# musicbox.net
KiCad netlist of a schematic drawn in EAGLE
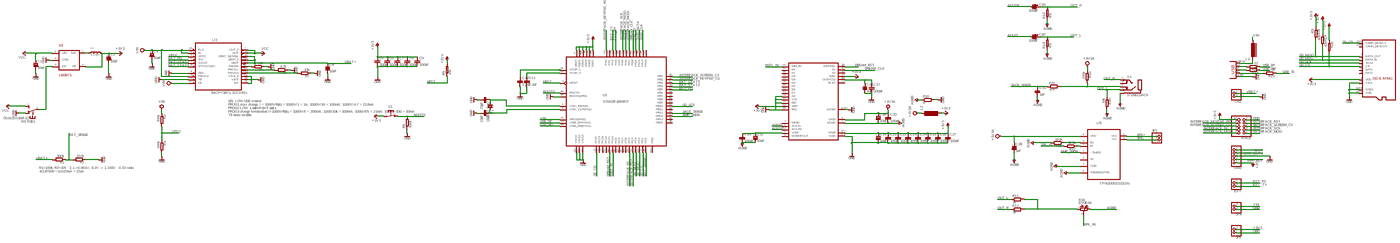
[diagram p0: schematic, sheet 1, overview]
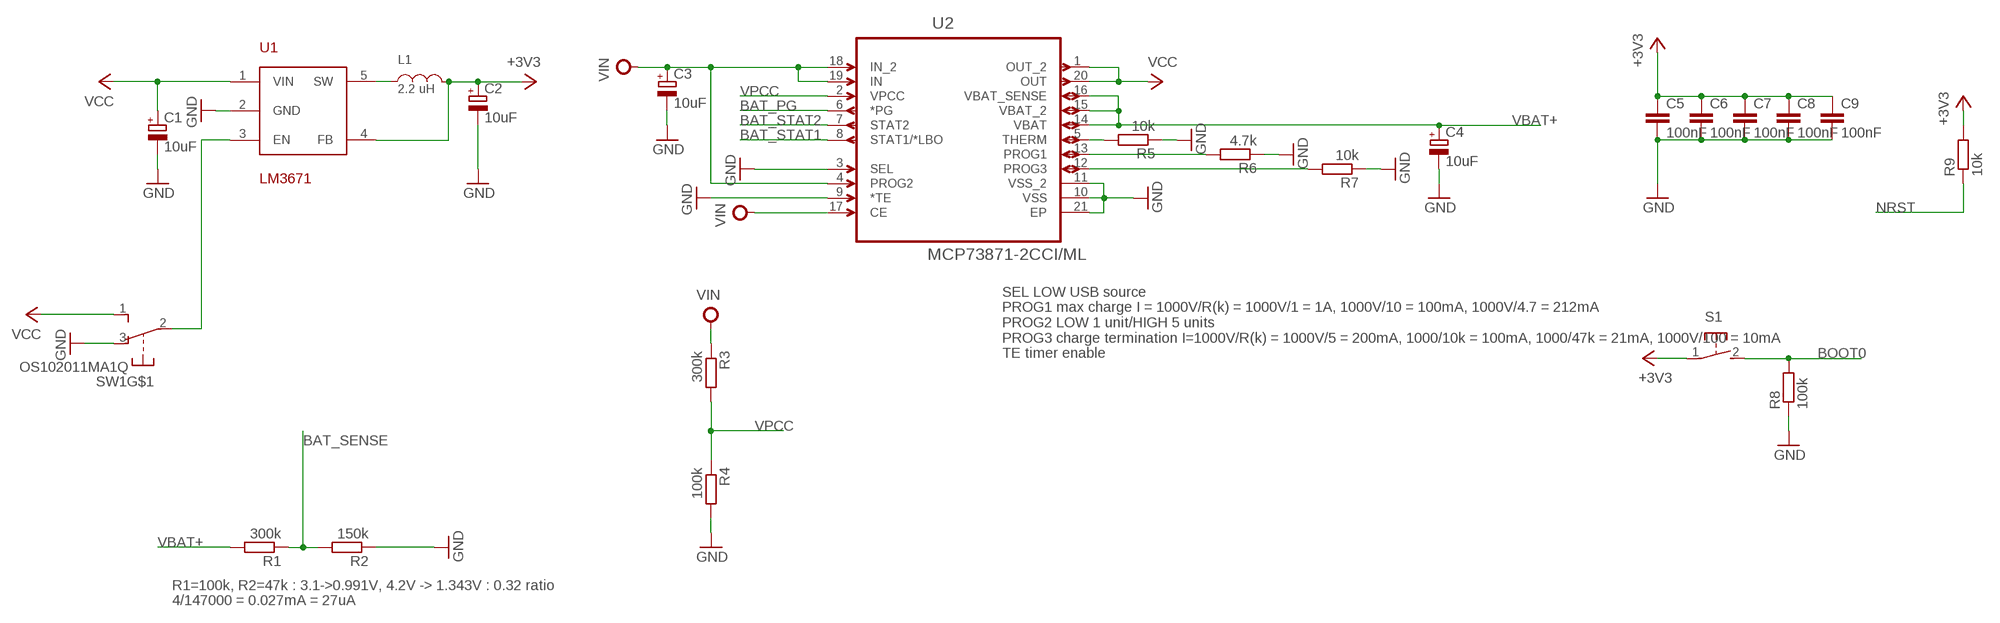
[diagram p1: schematic, sheet 1, part 1 of 4]
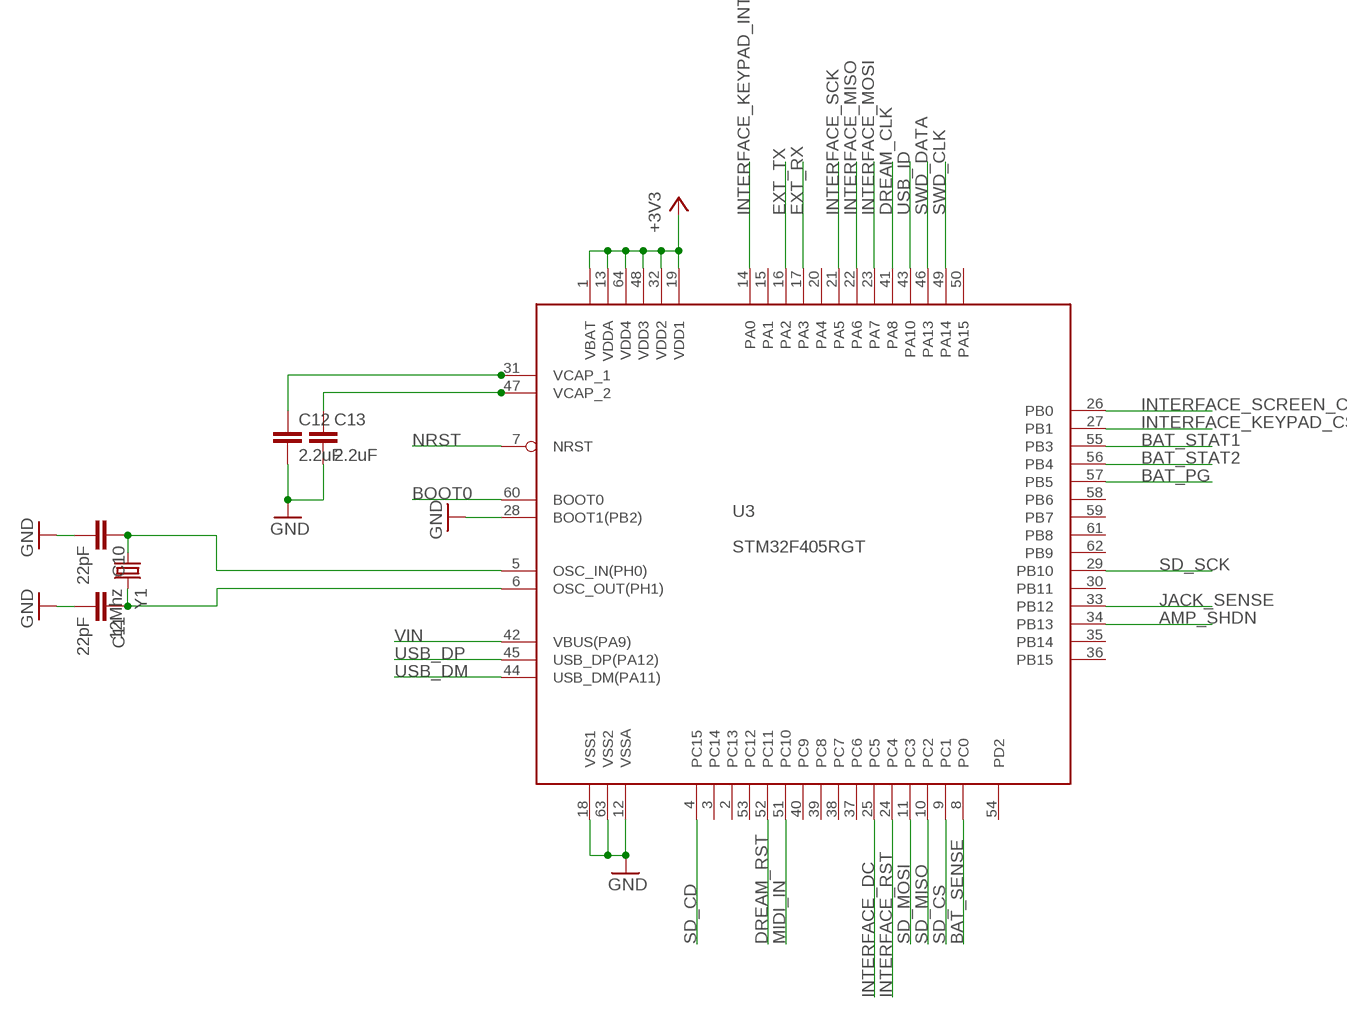
[diagram p2: schematic, sheet 1, part 2 of 4]
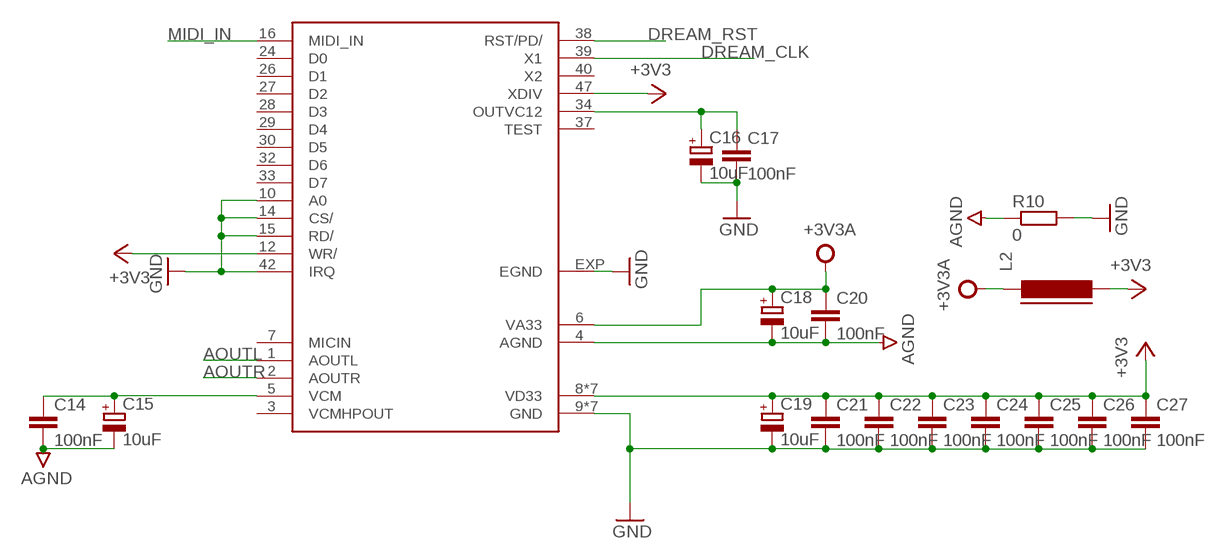
[diagram p3: schematic, sheet 1, part 3 of 4]
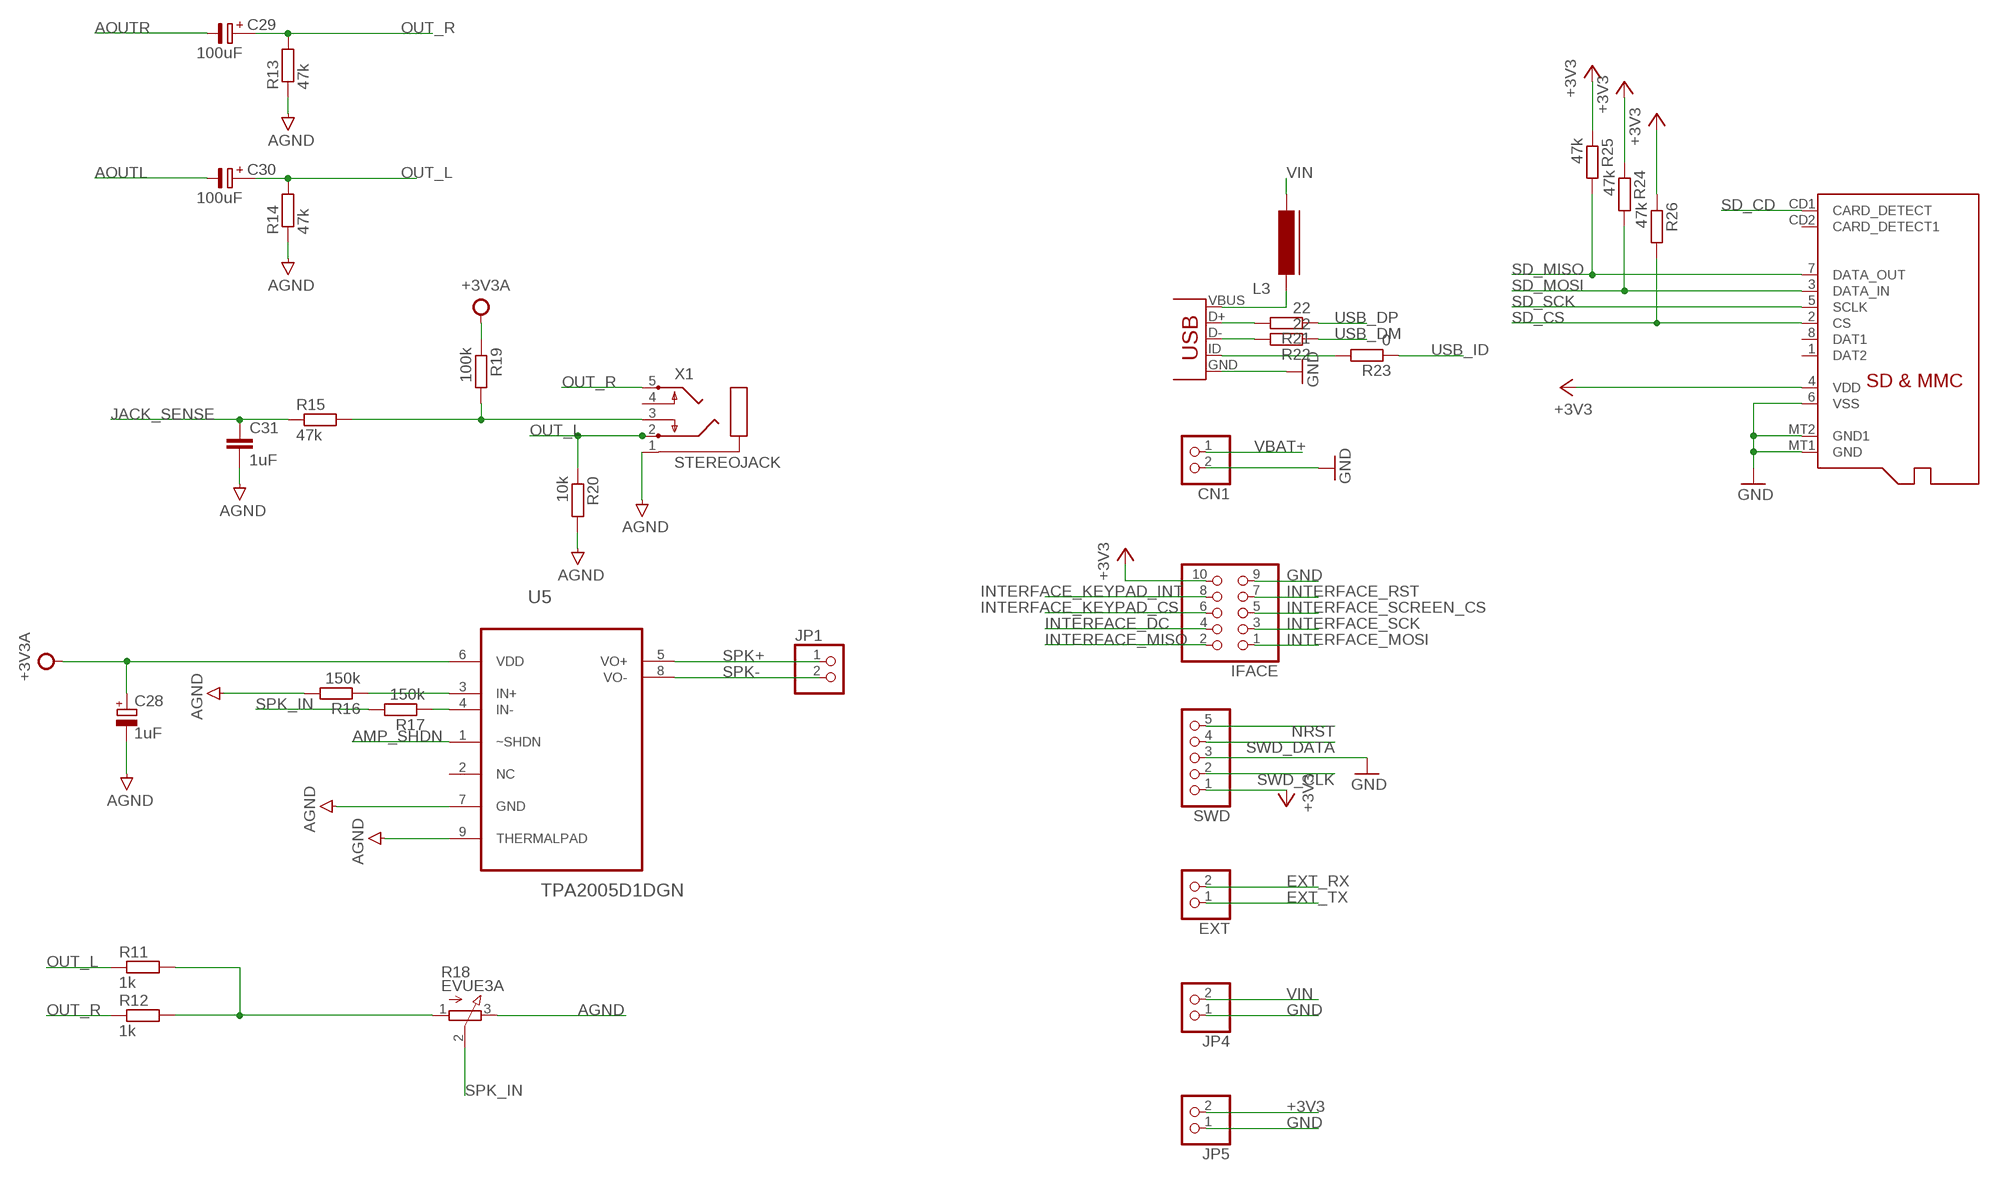
[diagram p4: schematic, sheet 1, part 4 of 4]

(export (version "E")
  (design (tool "Eeschema 10.0.6"))
  (components
    (comp (ref "C1")
      (value "10uF")
      (footprint "eagle-import:A_3216-18R")
      (libsource (lib "eagle-import") (part "CPOL-EUA/3216-18R"))
    )
    (comp (ref "C2")
      (value "10uF")
      (footprint "eagle-import:A_3216-18R")
      (libsource (lib "eagle-import") (part "CPOL-EUA/3216-18R"))
    )
    (comp (ref "C3")
      (value "10uF")
      (footprint "eagle-import:A_3216-18R")
      (libsource (lib "eagle-import") (part "CPOL-EUA/3216-18R"))
    )
    (comp (ref "C4")
      (value "10uF")
      (footprint "eagle-import:A_3216-18R")
      (libsource (lib "eagle-import") (part "CPOL-EUA/3216-18R"))
    )
    (comp (ref "C5")
      (value "100nF")
      (footprint "eagle-import:C0603K")
      (libsource (lib "eagle-import") (part "C-EUC0603K"))
    )
    (comp (ref "C6")
      (value "100nF")
      (footprint "eagle-import:C0603K")
      (libsource (lib "eagle-import") (part "C-EUC0603K"))
    )
    (comp (ref "C7")
      (value "100nF")
      (footprint "eagle-import:C0603K")
      (libsource (lib "eagle-import") (part "C-EUC0603K"))
    )
    (comp (ref "C8")
      (value "100nF")
      (footprint "eagle-import:C0603K")
      (libsource (lib "eagle-import") (part "C-EUC0603K"))
    )
    (comp (ref "C9")
      (value "100nF")
      (footprint "eagle-import:C0603K")
      (libsource (lib "eagle-import") (part "C-EUC0603K"))
    )
    (comp (ref "C10")
      (value "22pF")
      (footprint "eagle-import:C0603K")
      (libsource (lib "eagle-import") (part "C-EUC0603K"))
    )
    (comp (ref "C11")
      (value "22pF")
      (footprint "eagle-import:C0603K")
      (libsource (lib "eagle-import") (part "C-EUC0603K"))
    )
    (comp (ref "C12")
      (value "2.2uF")
      (footprint "eagle-import:C0603K")
      (libsource (lib "eagle-import") (part "C-EUC0603K"))
    )
    (comp (ref "C13")
      (value "2.2uF")
      (footprint "eagle-import:C0603K")
      (libsource (lib "eagle-import") (part "C-EUC0603K"))
    )
    (comp (ref "C14")
      (value "100nF")
      (footprint "eagle-import:C0603K")
      (libsource (lib "eagle-import") (part "C-EUC0603K"))
    )
    (comp (ref "C15")
      (value "10uF")
      (footprint "eagle-import:A_3216-18R")
      (libsource (lib "eagle-import") (part "CPOL-EUA/3216-18R"))
    )
    (comp (ref "C16")
      (value "10uF")
      (footprint "eagle-import:A_3216-18R")
      (libsource (lib "eagle-import") (part "CPOL-EUA/3216-18R"))
    )
    (comp (ref "C17")
      (value "100nF")
      (footprint "eagle-import:C0603K")
      (libsource (lib "eagle-import") (part "C-EUC0603K"))
    )
    (comp (ref "C18")
      (value "10uF")
      (footprint "eagle-import:A_3216-18R")
      (libsource (lib "eagle-import") (part "CPOL-EUA/3216-18R"))
    )
    (comp (ref "C19")
      (value "10uF")
      (footprint "eagle-import:A_3216-18R")
      (libsource (lib "eagle-import") (part "CPOL-EUA/3216-18R"))
    )
    (comp (ref "C20")
      (value "100nF")
      (footprint "eagle-import:C0603K")
      (libsource (lib "eagle-import") (part "C-EUC0603K"))
    )
    (comp (ref "C21")
      (value "100nF")
      (footprint "eagle-import:C0603K")
      (libsource (lib "eagle-import") (part "C-EUC0603K"))
    )
    (comp (ref "C22")
      (value "100nF")
      (footprint "eagle-import:C0603K")
      (libsource (lib "eagle-import") (part "C-EUC0603K"))
    )
    (comp (ref "C23")
      (value "100nF")
      (footprint "eagle-import:C0603K")
      (libsource (lib "eagle-import") (part "C-EUC0603K"))
    )
    (comp (ref "C24")
      (value "100nF")
      (footprint "eagle-import:C0603K")
      (libsource (lib "eagle-import") (part "C-EUC0603K"))
    )
    (comp (ref "C25")
      (value "100nF")
      (footprint "eagle-import:C0603K")
      (libsource (lib "eagle-import") (part "C-EUC0603K"))
    )
    (comp (ref "C26")
      (value "100nF")
      (footprint "eagle-import:C0603K")
      (libsource (lib "eagle-import") (part "C-EUC0603K"))
    )
    (comp (ref "C27")
      (value "100nF")
      (footprint "eagle-import:C0603K")
      (libsource (lib "eagle-import") (part "C-EUC0603K"))
    )
    (comp (ref "C28")
      (value "1uF")
      (footprint "eagle-import:A_3216-18R")
      (libsource (lib "eagle-import") (part "CPOL-EUA/3216-18R"))
    )
    (comp (ref "C29")
      (value "100uF")
      (footprint "eagle-import:SV-B")
      (libsource (lib "eagle-import") (part "C-PR-SMD-SV-B"))
    )
    (comp (ref "C30")
      (value "100uF")
      (footprint "eagle-import:SV-B")
      (libsource (lib "eagle-import") (part "C-PR-SMD-SV-B"))
    )
    (comp (ref "C31")
      (value "1uF")
      (footprint "eagle-import:C0603K")
      (libsource (lib "eagle-import") (part "C-EUC0603K"))
    )
    (comp (ref "CN1")
      (value "JST_2PIN-THM")
      (footprint "eagle-import:JST-PH-2-THM")
      (libsource (lib "eagle-import") (part "JST_2PIN-THM"))
    )
    (comp (ref "EXT")
      (value "HEADER-1X2ROUND")
      (footprint "eagle-import:1X02_ROUND")
      (libsource (lib "eagle-import") (part "HEADER-1X2ROUND"))
    )
    (comp (ref "IFACE")
      (value "HEADER-2X5")
      (footprint "eagle-import:2X05")
      (libsource (lib "eagle-import") (part "HEADER-2X5"))
    )
    (comp (ref "JP1")
      (value "HEADER-1X2ROUND")
      (footprint "eagle-import:1X02_ROUND")
      (libsource (lib "eagle-import") (part "HEADER-1X2ROUND"))
    )
    (comp (ref "JP4")
      (value "HEADER-1X2ROUND")
      (footprint "eagle-import:1X02_ROUND")
      (libsource (lib "eagle-import") (part "HEADER-1X2ROUND"))
    )
    (comp (ref "JP5")
      (value "HEADER-1X2ROUND")
      (footprint "eagle-import:1X02_ROUND")
      (libsource (lib "eagle-import") (part "HEADER-1X2ROUND"))
    )
    (comp (ref "L1")
      (value "2.2 uH")
      (footprint "eagle-import:4X4MM")
      (libsource (lib "eagle-import") (part "L4X4MM"))
    )
    (comp (ref "L2")
      (value "FERRITE-0603")
      (footprint "eagle-import:FB603")
      (libsource (lib "eagle-import") (part "FERRITE-0603"))
    )
    (comp (ref "L3")
      (value "FERRITE-0603")
      (footprint "eagle-import:FB603")
      (libsource (lib "eagle-import") (part "FERRITE-0603"))
    )
    (comp (ref "R1")
      (value "300k")
      (footprint "eagle-import:R0603")
      (libsource (lib "eagle-import") (part "R-EU_R0603"))
    )
    (comp (ref "R2")
      (value "150k")
      (footprint "eagle-import:R0603")
      (libsource (lib "eagle-import") (part "R-EU_R0603"))
    )
    (comp (ref "R3")
      (value "300k")
      (footprint "eagle-import:R0603")
      (libsource (lib "eagle-import") (part "R-EU_R0603"))
    )
    (comp (ref "R4")
      (value "100k")
      (footprint "eagle-import:R0603")
      (libsource (lib "eagle-import") (part "R-EU_R0603"))
    )
    (comp (ref "R5")
      (value "10k")
      (footprint "eagle-import:R0603")
      (libsource (lib "eagle-import") (part "R-EU_R0603"))
    )
    (comp (ref "R6")
      (value "4.7k")
      (footprint "eagle-import:R0603")
      (libsource (lib "eagle-import") (part "R-EU_R0603"))
    )
    (comp (ref "R7")
      (value "10k")
      (footprint "eagle-import:R0603")
      (libsource (lib "eagle-import") (part "R-EU_R0603"))
    )
    (comp (ref "R8")
      (value "100k")
      (footprint "eagle-import:R0603")
      (libsource (lib "eagle-import") (part "R-EU_R0603"))
    )
    (comp (ref "R9")
      (value "10k")
      (footprint "eagle-import:R0603")
      (libsource (lib "eagle-import") (part "R-EU_R0603"))
    )
    (comp (ref "R10")
      (value "0")
      (footprint "eagle-import:R0603")
      (libsource (lib "eagle-import") (part "R-EU_R0603"))
    )
    (comp (ref "R11")
      (value "1k")
      (footprint "eagle-import:R0603")
      (libsource (lib "eagle-import") (part "R-EU_R0603"))
    )
    (comp (ref "R12")
      (value "1k")
      (footprint "eagle-import:R0603")
      (libsource (lib "eagle-import") (part "R-EU_R0603"))
    )
    (comp (ref "R13")
      (value "47k")
      (footprint "eagle-import:R0603")
      (libsource (lib "eagle-import") (part "R-EU_R0603"))
    )
    (comp (ref "R14")
      (value "47k")
      (footprint "eagle-import:R0603")
      (libsource (lib "eagle-import") (part "R-EU_R0603"))
    )
    (comp (ref "R15")
      (value "47k")
      (footprint "eagle-import:R0603")
      (libsource (lib "eagle-import") (part "R-EU_R0603"))
    )
    (comp (ref "R16")
      (value "150k")
      (footprint "eagle-import:R0603")
      (libsource (lib "eagle-import") (part "R-EU_R0603"))
    )
    (comp (ref "R17")
      (value "150k")
      (footprint "eagle-import:R0603")
      (libsource (lib "eagle-import") (part "R-EU_R0603"))
    )
    (comp (ref "R18")
      (value "EVUE3A")
      (footprint "eagle-import:EVUE")
      (libsource (lib "eagle-import") (part "EVUE3A"))
    )
    (comp (ref "R19")
      (value "100k")
      (footprint "eagle-import:R0603")
      (libsource (lib "eagle-import") (part "R-EU_R0603"))
    )
    (comp (ref "R20")
      (value "10k")
      (footprint "eagle-import:R0603")
      (libsource (lib "eagle-import") (part "R-EU_R0603"))
    )
    (comp (ref "R21")
      (value "22")
      (footprint "eagle-import:R0603")
      (libsource (lib "eagle-import") (part "R-EU_R0603"))
    )
    (comp (ref "R22")
      (value "22")
      (footprint "eagle-import:R0603")
      (libsource (lib "eagle-import") (part "R-EU_R0603"))
    )
    (comp (ref "R23")
      (value "0")
      (footprint "eagle-import:R0603")
      (libsource (lib "eagle-import") (part "R-EU_R0603"))
    )
    (comp (ref "R24")
      (value "47k")
      (footprint "eagle-import:R0603")
      (libsource (lib "eagle-import") (part "R-EU_R0603"))
    )
    (comp (ref "R25")
      (value "47k")
      (footprint "eagle-import:R0603")
      (libsource (lib "eagle-import") (part "R-EU_R0603"))
    )
    (comp (ref "R26")
      (value "47k")
      (footprint "eagle-import:R0603")
      (libsource (lib "eagle-import") (part "R-EU_R0603"))
    )
    (comp (ref "S1")
      (value "31-XX")
      (footprint "eagle-import:B3F-31XX")
      (fields (field (name "MPN") "B3F-3100"))
      (libsource (lib "eagle-import") (part "31-XX"))
    )
    (comp (ref "SW1")
      (value "OS102011MA1Q")
      (footprint "eagle-import:OS102011MA1Q")
      (libsource (lib "eagle-import") (part "OS102011MA1Q"))
    )
    (comp (ref "SWD")
      (value "HEADER-1X5ROUND")
      (footprint "eagle-import:1X05_ROUND")
      (libsource (lib "eagle-import") (part "HEADER-1X5ROUND"))
    )
    (comp (ref "U1")
      (value "LM3671")
      (footprint "eagle-import:SOT23-5")
      (libsource (lib "eagle-import") (part "LM3671"))
    )
    (comp (ref "U2")
      (value "MCP73871-2CCI/ML")
      (footprint "eagle-import:QFN50P400X400X100-21N")
      (libsource (lib "eagle-import") (part "MCP73871-2CCI/ML"))
    )
    (comp (ref "U3")
      (value "STM32F405RGT")
      (footprint "eagle-import:LQFP64")
      (libsource (lib "eagle-import") (part "STM32F405RGT"))
    )
    (comp (ref "U4")
      (value "SAM2695")
      (footprint "eagle-import:QFN48")
      (libsource (lib "eagle-import") (part "SAM2695"))
    )
    (comp (ref "U5")
      (value "TPA2005D1DGN")
      (footprint "eagle-import:SOP65P488X107-9N")
      (libsource (lib "eagle-import") (part "TPA2005D1DGN"))
    )
    (comp (ref "U6")
      (value "MICROSD")
      (footprint "eagle-import:MICROSD")
      (libsource (lib "eagle-import") (part "MICROSD"))
    )
    (comp (ref "X1")
      (value "STEREOJACK")
      (footprint "eagle-import:STX3100")
      (libsource (lib "eagle-import") (part "STEREOJACK"))
    )
    (comp (ref "X2")
      (value "USB-MICROB-SMD")
      (footprint "eagle-import:USB-MICROB-SMD")
      (libsource (lib "eagle-import") (part "USB-MICROB-SMD"))
    )
    (comp (ref "Y1")
      (value "12Mhz")
      (footprint "eagle-import:CRYSTAL-TXC-7A")
      (libsource (lib "eagle-import") (part "CRYSTALTXC-7A"))
    )
  )
  (nets
    (net (code "1") (name "+3V3") (class "Default")
      (node (ref "C19") (pin "+") (pinfunction "+_+") (pintype "passive"))
      (node (ref "C2") (pin "+") (pinfunction "+_+") (pintype "passive"))
      (node (ref "C21") (pin "1") (pinfunction "1_1") (pintype "passive"))
      (node (ref "C22") (pin "1") (pinfunction "1_1") (pintype "passive"))
      (node (ref "C23") (pin "1") (pinfunction "1_1") (pintype "passive"))
      (node (ref "C24") (pin "1") (pinfunction "1_1") (pintype "passive"))
      (node (ref "C25") (pin "1") (pinfunction "1_1") (pintype "passive"))
      (node (ref "C26") (pin "1") (pinfunction "1_1") (pintype "passive"))
      (node (ref "C27") (pin "1") (pinfunction "1_1") (pintype "passive"))
      (node (ref "C5") (pin "1") (pinfunction "1_1") (pintype "passive"))
      (node (ref "C6") (pin "1") (pinfunction "1_1") (pintype "passive"))
      (node (ref "C7") (pin "1") (pinfunction "1_1") (pintype "passive"))
      (node (ref "C8") (pin "1") (pinfunction "1_1") (pintype "passive"))
      (node (ref "C9") (pin "1") (pinfunction "1_1") (pintype "passive"))
      (node (ref "IFACE") (pin "10") (pinfunction "10_10") (pintype "passive"))
      (node (ref "JP5") (pin "2") (pinfunction "2_2") (pintype "passive"))
      (node (ref "L1") (pin "2") (pinfunction "2_2") (pintype "passive"))
      (node (ref "L2") (pin "2") (pinfunction "2_2") (pintype "passive"))
      (node (ref "R24") (pin "1") (pinfunction "1_1") (pintype "passive"))
      (node (ref "R25") (pin "1") (pinfunction "1_1") (pintype "passive"))
      (node (ref "R26") (pin "1") (pinfunction "1_1") (pintype "passive"))
      (node (ref "R9") (pin "2") (pinfunction "2_2") (pintype "passive"))
      (node (ref "S1") (pin "1") (pinfunction "P_1") (pintype "passive"))
      (node (ref "SWD") (pin "1") (pinfunction "1_1") (pintype "passive"))
      (node (ref "U1") (pin "4") (pinfunction "FB_4") (pintype "bidirectional"))
      (node (ref "U3") (pin "1") (pinfunction "VBAT_1") (pintype "power_in"))
      (node (ref "U3") (pin "13") (pinfunction "VDDA_13") (pintype "power_in"))
      (node (ref "U3") (pin "19") (pinfunction "VDD1_19") (pintype "power_in"))
      (node (ref "U3") (pin "32") (pinfunction "VDD2_32") (pintype "power_in"))
      (node (ref "U3") (pin "48") (pinfunction "VDD3_48") (pintype "power_in"))
      (node (ref "U3") (pin "64") (pinfunction "VDD4_64") (pintype "power_in"))
      (node (ref "U4") (pin "11") (pinfunction "VD33_11") (pintype "power_in"))
      (node (ref "U4") (pin "12") (pinfunction "WR/_12") (pintype "input"))
      (node (ref "U4") (pin "20") (pinfunction "VD33_20") (pintype "power_in"))
      (node (ref "U4") (pin "31") (pinfunction "VD33_31") (pintype "power_in"))
      (node (ref "U4") (pin "35") (pinfunction "VD33_35") (pintype "power_in"))
      (node (ref "U4") (pin "41") (pinfunction "VD33_41") (pintype "power_in"))
      (node (ref "U4") (pin "46") (pinfunction "VD33_46") (pintype "power_in"))
      (node (ref "U4") (pin "47") (pinfunction "XDIV_47") (pintype "input"))
      (node (ref "U4") (pin "8") (pinfunction "VD33_8") (pintype "power_in"))
      (node (ref "U6") (pin "4") (pinfunction "VDD_4") (pintype "power_in"))
    )
    (net (code "2") (name "+3V3A") (class "Default")
      (node (ref "C18") (pin "+") (pinfunction "+_+") (pintype "passive"))
      (node (ref "C20") (pin "1") (pinfunction "1_1") (pintype "passive"))
      (node (ref "C28") (pin "+") (pinfunction "+_+") (pintype "passive"))
      (node (ref "L2") (pin "1") (pinfunction "1_1") (pintype "passive"))
      (node (ref "R19") (pin "1") (pinfunction "1_1") (pintype "passive"))
      (node (ref "U4") (pin "6") (pinfunction "VA33_6") (pintype "power_in"))
      (node (ref "U5") (pin "6") (pinfunction "VDD_6") (pintype "power_in"))
    )
    (net (code "3") (name "/AMP_SHDN") (class "Default")
      (node (ref "U3") (pin "34") (pinfunction "PB13_34") (pintype "bidirectional"))
      (node (ref "U5") (pin "1") (pinfunction "~{SHDN}_1") (pintype "passive"))
    )
    (net (code "4") (name "/AOUTL") (class "Default")
      (node (ref "C30") (pin "-") (pinfunction "-_-") (pintype "passive"))
      (node (ref "U4") (pin "1") (pinfunction "AOUTL_1") (pintype "output"))
    )
    (net (code "5") (name "/AOUTR") (class "Default")
      (node (ref "C29") (pin "-") (pinfunction "-_-") (pintype "passive"))
      (node (ref "U4") (pin "2") (pinfunction "AOUTR_2") (pintype "output"))
    )
    (net (code "6") (name "/BAT_PG") (class "Default")
      (node (ref "U2") (pin "6") (pinfunction "*PG_6") (pintype "output"))
      (node (ref "U3") (pin "57") (pinfunction "PB5_57") (pintype "bidirectional"))
    )
    (net (code "7") (name "/BAT_SENSE") (class "Default")
      (node (ref "R1") (pin "1") (pinfunction "1_1") (pintype "passive"))
      (node (ref "R2") (pin "2") (pinfunction "2_2") (pintype "passive"))
      (node (ref "U3") (pin "8") (pinfunction "PC0_8") (pintype "bidirectional"))
    )
    (net (code "8") (name "/BAT_STAT1") (class "Default")
      (node (ref "U2") (pin "8") (pinfunction "STAT1/*LBO_8") (pintype "output"))
      (node (ref "U3") (pin "55") (pinfunction "PB3_55") (pintype "bidirectional"))
    )
    (net (code "9") (name "/BAT_STAT2") (class "Default")
      (node (ref "U2") (pin "7") (pinfunction "STAT2_7") (pintype "output"))
      (node (ref "U3") (pin "56") (pinfunction "PB4_56") (pintype "bidirectional"))
    )
    (net (code "10") (name "/BOOT0") (class "Default")
      (node (ref "R8") (pin "2") (pinfunction "2_2") (pintype "passive"))
      (node (ref "S1") (pin "2") (pinfunction "S_2") (pintype "passive"))
      (node (ref "U3") (pin "60") (pinfunction "BOOT0_60") (pintype "input"))
    )
    (net (code "11") (name "/DREAM_CLK") (class "Default")
      (node (ref "U3") (pin "41") (pinfunction "PA8_41") (pintype "bidirectional"))
      (node (ref "U4") (pin "39") (pinfunction "X1_39") (pintype "bidirectional"))
    )
    (net (code "12") (name "/DREAM_RST") (class "Default")
      (node (ref "U3") (pin "52") (pinfunction "PC11_52") (pintype "bidirectional"))
      (node (ref "U4") (pin "38") (pinfunction "RST/PD/_38") (pintype "input"))
    )
    (net (code "13") (name "/EXT_RX") (class "Default")
      (node (ref "EXT") (pin "2") (pinfunction "2_2") (pintype "passive"))
      (node (ref "U3") (pin "17") (pinfunction "PA3_17") (pintype "bidirectional"))
    )
    (net (code "14") (name "/EXT_TX") (class "Default")
      (node (ref "EXT") (pin "1") (pinfunction "1_1") (pintype "passive"))
      (node (ref "U3") (pin "16") (pinfunction "PA2_16") (pintype "bidirectional"))
    )
    (net (code "15") (name "/INTERFACE_DC") (class "Default")
      (node (ref "IFACE") (pin "4") (pinfunction "4_4") (pintype "passive"))
      (node (ref "U3") (pin "25") (pinfunction "PC5_25") (pintype "bidirectional"))
    )
    (net (code "16") (name "/INTERFACE_KEYPAD_CS") (class "Default")
      (node (ref "IFACE") (pin "6") (pinfunction "6_6") (pintype "passive"))
      (node (ref "U3") (pin "27") (pinfunction "PB1_27") (pintype "bidirectional"))
    )
    (net (code "17") (name "/INTERFACE_KEYPAD_INT") (class "Default")
      (node (ref "IFACE") (pin "8") (pinfunction "8_8") (pintype "passive"))
      (node (ref "U3") (pin "14") (pinfunction "PA0_14") (pintype "bidirectional"))
    )
    (net (code "18") (name "/INTERFACE_MISO") (class "Default")
      (node (ref "IFACE") (pin "2") (pinfunction "2_2") (pintype "passive"))
      (node (ref "U3") (pin "22") (pinfunction "PA6_22") (pintype "bidirectional"))
    )
    (net (code "19") (name "/INTERFACE_MOSI") (class "Default")
      (node (ref "IFACE") (pin "1") (pinfunction "1_1") (pintype "passive"))
      (node (ref "U3") (pin "23") (pinfunction "PA7_23") (pintype "bidirectional"))
    )
    (net (code "20") (name "/INTERFACE_RST") (class "Default")
      (node (ref "IFACE") (pin "7") (pinfunction "7_7") (pintype "passive"))
      (node (ref "U3") (pin "24") (pinfunction "PC4_24") (pintype "bidirectional"))
    )
    (net (code "21") (name "/INTERFACE_SCK") (class "Default")
      (node (ref "IFACE") (pin "3") (pinfunction "3_3") (pintype "passive"))
      (node (ref "U3") (pin "21") (pinfunction "PA5_21") (pintype "bidirectional"))
    )
    (net (code "22") (name "/INTERFACE_SCREEN_CS") (class "Default")
      (node (ref "IFACE") (pin "5") (pinfunction "5_5") (pintype "passive"))
      (node (ref "U3") (pin "26") (pinfunction "PB0_26") (pintype "bidirectional"))
    )
    (net (code "23") (name "/JACK_SENSE") (class "Default")
      (node (ref "C31") (pin "1") (pinfunction "1_1") (pintype "passive"))
      (node (ref "R15") (pin "1") (pinfunction "1_1") (pintype "passive"))
      (node (ref "U3") (pin "33") (pinfunction "PB12_33") (pintype "bidirectional"))
    )
    (net (code "24") (name "/MIDI_IN") (class "Default")
      (node (ref "U3") (pin "51") (pinfunction "PC10_51") (pintype "bidirectional"))
      (node (ref "U4") (pin "16") (pinfunction "MIDI_IN_16") (pintype "input"))
    )
    (net (code "25") (name "/NRST") (class "Default")
      (node (ref "R9") (pin "1") (pinfunction "1_1") (pintype "passive"))
      (node (ref "SWD") (pin "5") (pinfunction "5_5") (pintype "passive"))
      (node (ref "U3") (pin "7") (pinfunction "NRST_7") (pintype "input"))
    )
    (net (code "26") (name "/OUT_L") (class "Default")
      (node (ref "C30") (pin "+") (pinfunction "+_+") (pintype "passive"))
      (node (ref "R11") (pin "1") (pinfunction "1_1") (pintype "passive"))
      (node (ref "R14") (pin "2") (pinfunction "2_2") (pintype "passive"))
      (node (ref "R20") (pin "1") (pinfunction "1_1") (pintype "passive"))
      (node (ref "X1") (pin "2") (pinfunction "2_2") (pintype "passive"))
    )
    (net (code "27") (name "/OUT_R") (class "Default")
      (node (ref "C29") (pin "+") (pinfunction "+_+") (pintype "passive"))
      (node (ref "R12") (pin "1") (pinfunction "1_1") (pintype "passive"))
      (node (ref "R13") (pin "2") (pinfunction "2_2") (pintype "passive"))
      (node (ref "X1") (pin "5") (pinfunction "5_5") (pintype "passive"))
    )
    (net (code "28") (name "/SD_CD") (class "Default")
      (node (ref "U3") (pin "4") (pinfunction "PC15_4") (pintype "bidirectional"))
      (node (ref "U6") (pin "CD1") (pinfunction "CARD_DETECT_CD1") (pintype "passive"))
    )
    (net (code "29") (name "/SD_CS") (class "Default")
      (node (ref "R26") (pin "2") (pinfunction "2_2") (pintype "passive"))
      (node (ref "U3") (pin "9") (pinfunction "PC1_9") (pintype "bidirectional"))
      (node (ref "U6") (pin "2") (pinfunction "CS_2") (pintype "input"))
    )
    (net (code "30") (name "/SD_MISO") (class "Default")
      (node (ref "R25") (pin "2") (pinfunction "2_2") (pintype "passive"))
      (node (ref "U3") (pin "10") (pinfunction "PC2_10") (pintype "bidirectional"))
      (node (ref "U6") (pin "7") (pinfunction "DATA_OUT_7") (pintype "output"))
    )
    (net (code "31") (name "/SD_MOSI") (class "Default")
      (node (ref "R24") (pin "2") (pinfunction "2_2") (pintype "passive"))
      (node (ref "U3") (pin "11") (pinfunction "PC3_11") (pintype "bidirectional"))
      (node (ref "U6") (pin "3") (pinfunction "DATA_IN_3") (pintype "input"))
    )
    (net (code "32") (name "/SD_SCK") (class "Default")
      (node (ref "U3") (pin "29") (pinfunction "PB10_29") (pintype "bidirectional"))
      (node (ref "U6") (pin "5") (pinfunction "SCLK_5") (pintype "input"))
    )
    (net (code "33") (name "/SPK+") (class "Default")
      (node (ref "JP1") (pin "1") (pinfunction "1_1") (pintype "passive"))
      (node (ref "U5") (pin "5") (pinfunction "VO+_5") (pintype "output"))
    )
    (net (code "34") (name "/SPK-") (class "Default")
      (node (ref "JP1") (pin "2") (pinfunction "2_2") (pintype "passive"))
      (node (ref "U5") (pin "8") (pinfunction "VO-_8") (pintype "output"))
    )
    (net (code "35") (name "/SPK_IN") (class "Default")
      (node (ref "R17") (pin "2") (pinfunction "2_2") (pintype "passive"))
      (node (ref "R18") (pin "2") (pinfunction "S_2") (pintype "passive"))
    )
    (net (code "36") (name "/SWD_CLK") (class "Default")
      (node (ref "SWD") (pin "2") (pinfunction "2_2") (pintype "passive"))
      (node (ref "U3") (pin "49") (pinfunction "PA14_49") (pintype "bidirectional"))
    )
    (net (code "37") (name "/SWD_DATA") (class "Default")
      (node (ref "SWD") (pin "4") (pinfunction "4_4") (pintype "passive"))
      (node (ref "U3") (pin "46") (pinfunction "PA13_46") (pintype "bidirectional"))
    )
    (net (code "38") (name "/USB_DM") (class "Default")
      (node (ref "R22") (pin "1") (pinfunction "1_1") (pintype "passive"))
      (node (ref "U3") (pin "44") (pinfunction "USB_DM(PA11)_44") (pintype "bidirectional"))
    )
    (net (code "39") (name "/USB_DP") (class "Default")
      (node (ref "R21") (pin "1") (pinfunction "1_1") (pintype "passive"))
      (node (ref "U3") (pin "45") (pinfunction "USB_DP(PA12)_45") (pintype "bidirectional"))
    )
    (net (code "40") (name "/USB_ID") (class "Default")
      (node (ref "R23") (pin "1") (pinfunction "1_1") (pintype "passive"))
      (node (ref "U3") (pin "43") (pinfunction "PA10_43") (pintype "bidirectional"))
    )
    (net (code "41") (name "/VBAT+") (class "Default")
      (node (ref "C4") (pin "+") (pinfunction "+_+") (pintype "passive"))
      (node (ref "CN1") (pin "1") (pinfunction "2_1") (pintype "passive"))
      (node (ref "R1") (pin "2") (pinfunction "2_2") (pintype "passive"))
      (node (ref "U2") (pin "14") (pinfunction "VBAT_14") (pintype "bidirectional"))
      (node (ref "U2") (pin "15") (pinfunction "VBAT_2_15") (pintype "bidirectional"))
      (node (ref "U2") (pin "16") (pinfunction "VBAT_SENSE_16") (pintype "bidirectional"))
    )
    (net (code "42") (name "/VPCC") (class "Default")
      (node (ref "R3") (pin "2") (pinfunction "2_2") (pintype "passive"))
      (node (ref "R4") (pin "1") (pinfunction "1_1") (pintype "passive"))
      (node (ref "U2") (pin "2") (pinfunction "VPCC_2") (pintype "input"))
    )
    (net (code "43") (name "AGND") (class "Default")
      (node (ref "C14") (pin "2") (pinfunction "2_2") (pintype "passive"))
      (node (ref "C15") (pin "-") (pinfunction "-_-") (pintype "passive"))
      (node (ref "C18") (pin "-") (pinfunction "-_-") (pintype "passive"))
      (node (ref "C20") (pin "2") (pinfunction "2_2") (pintype "passive"))
      (node (ref "C28") (pin "-") (pinfunction "-_-") (pintype "passive"))
      (node (ref "C31") (pin "2") (pinfunction "2_2") (pintype "passive"))
      (node (ref "R10") (pin "1") (pinfunction "1_1") (pintype "passive"))
      (node (ref "R13") (pin "1") (pinfunction "1_1") (pintype "passive"))
      (node (ref "R14") (pin "1") (pinfunction "1_1") (pintype "passive"))
      (node (ref "R16") (pin "2") (pinfunction "2_2") (pintype "passive"))
      (node (ref "R18") (pin "3") (pinfunction "E_3") (pintype "passive"))
      (node (ref "R20") (pin "2") (pinfunction "2_2") (pintype "passive"))
      (node (ref "U4") (pin "4") (pinfunction "AGND_4") (pintype "power_in"))
      (node (ref "U5") (pin "7") (pinfunction "GND_7") (pintype "passive"))
      (node (ref "U5") (pin "9") (pinfunction "THERMALPAD_9") (pintype "passive"))
      (node (ref "X1") (pin "1") (pinfunction "1_1") (pintype "passive"))
    )
    (net (code "44") (name "GND") (class "Default")
      (node (ref "C1") (pin "-") (pinfunction "-_-") (pintype "passive"))
      (node (ref "C10") (pin "2") (pinfunction "2_2") (pintype "passive"))
      (node (ref "C11") (pin "2") (pinfunction "2_2") (pintype "passive"))
      (node (ref "C12") (pin "2") (pinfunction "2_2") (pintype "passive"))
      (node (ref "C13") (pin "2") (pinfunction "2_2") (pintype "passive"))
      (node (ref "C16") (pin "-") (pinfunction "-_-") (pintype "passive"))
      (node (ref "C17") (pin "2") (pinfunction "2_2") (pintype "passive"))
      (node (ref "C19") (pin "-") (pinfunction "-_-") (pintype "passive"))
      (node (ref "C2") (pin "-") (pinfunction "-_-") (pintype "passive"))
      (node (ref "C21") (pin "2") (pinfunction "2_2") (pintype "passive"))
      (node (ref "C22") (pin "2") (pinfunction "2_2") (pintype "passive"))
      (node (ref "C23") (pin "2") (pinfunction "2_2") (pintype "passive"))
      (node (ref "C24") (pin "2") (pinfunction "2_2") (pintype "passive"))
      (node (ref "C25") (pin "2") (pinfunction "2_2") (pintype "passive"))
      (node (ref "C26") (pin "2") (pinfunction "2_2") (pintype "passive"))
      (node (ref "C27") (pin "2") (pinfunction "2_2") (pintype "passive"))
      (node (ref "C3") (pin "-") (pinfunction "-_-") (pintype "passive"))
      (node (ref "C4") (pin "-") (pinfunction "-_-") (pintype "passive"))
      (node (ref "C5") (pin "2") (pinfunction "2_2") (pintype "passive"))
      (node (ref "C6") (pin "2") (pinfunction "2_2") (pintype "passive"))
      (node (ref "C7") (pin "2") (pinfunction "2_2") (pintype "passive"))
      (node (ref "C8") (pin "2") (pinfunction "2_2") (pintype "passive"))
      (node (ref "C9") (pin "2") (pinfunction "2_2") (pintype "passive"))
      (node (ref "CN1") (pin "2") (pinfunction "1_2") (pintype "passive"))
      (node (ref "IFACE") (pin "9") (pinfunction "9_9") (pintype "passive"))
      (node (ref "JP4") (pin "1") (pinfunction "1_1") (pintype "passive"))
      (node (ref "JP5") (pin "1") (pinfunction "1_1") (pintype "passive"))
      (node (ref "R10") (pin "2") (pinfunction "2_2") (pintype "passive"))
      (node (ref "R2") (pin "1") (pinfunction "1_1") (pintype "passive"))
      (node (ref "R4") (pin "2") (pinfunction "2_2") (pintype "passive"))
      (node (ref "R5") (pin "1") (pinfunction "1_1") (pintype "passive"))
      (node (ref "R6") (pin "1") (pinfunction "1_1") (pintype "passive"))
      (node (ref "R7") (pin "1") (pinfunction "1_1") (pintype "passive"))
      (node (ref "R8") (pin "1") (pinfunction "1_1") (pintype "passive"))
      (node (ref "SW1") (pin "3") (pinfunction "O_3") (pintype "passive"))
      (node (ref "SWD") (pin "3") (pinfunction "3_3") (pintype "passive"))
      (node (ref "U1") (pin "2") (pinfunction "GND_2") (pintype "bidirectional"))
      (node (ref "U2") (pin "10") (pinfunction "VSS_10") (pintype "power_in"))
      (node (ref "U2") (pin "11") (pinfunction "VSS_2_11") (pintype "power_in"))
      (node (ref "U2") (pin "21") (pinfunction "EP_21") (pintype "passive"))
      (node (ref "U2") (pin "3") (pinfunction "SEL_3") (pintype "input"))
      (node (ref "U2") (pin "9") (pinfunction "*TE_9") (pintype "input"))
      (node (ref "U3") (pin "12") (pinfunction "VSSA_12") (pintype "power_in"))
      (node (ref "U3") (pin "18") (pinfunction "VSS1_18") (pintype "power_in"))
      (node (ref "U3") (pin "28") (pinfunction "BOOT1(PB2)_28") (pintype "input"))
      (node (ref "U3") (pin "63") (pinfunction "VSS2_63") (pintype "power_in"))
      (node (ref "U4") (pin "10") (pinfunction "A0_10") (pintype "input"))
      (node (ref "U4") (pin "13") (pinfunction "GND_13") (pintype "power_in"))
      (node (ref "U4") (pin "14") (pinfunction "CS/_14") (pintype "input"))
      (node (ref "U4") (pin "15") (pinfunction "RD/_15") (pintype "input"))
      (node (ref "U4") (pin "18") (pinfunction "GND_18") (pintype "power_in"))
      (node (ref "U4") (pin "25") (pinfunction "GND_25") (pintype "power_in"))
      (node (ref "U4") (pin "36") (pinfunction "GND_36") (pintype "power_in"))
      (node (ref "U4") (pin "42") (pinfunction "IRQ_42") (pintype "output"))
      (node (ref "U4") (pin "45") (pinfunction "GND_45") (pintype "power_in"))
      (node (ref "U4") (pin "48") (pinfunction "GND_48") (pintype "power_in"))
      (node (ref "U4") (pin "9") (pinfunction "GND_9") (pintype "power_in"))
      (node (ref "U4") (pin "EXP") (pinfunction "EGND_EXP") (pintype "power_in"))
      (node (ref "U6") (pin "6") (pinfunction "VSS_6") (pintype "power_in"))
      (node (ref "U6") (pin "MT1") (pinfunction "GND_MT1") (pintype "power_in"))
      (node (ref "U6") (pin "MT2") (pinfunction "GND1_MT2") (pintype "power_in"))
      (node (ref "X2") (pin "GND") (pinfunction "GND_GND") (pintype "bidirectional"))
    )
    (net (code "45") (name "Net-(L3-Pad1)") (class "Default")
      (node (ref "L3") (pin "1") (pinfunction "1_1") (pintype "passive"))
      (node (ref "X2") (pin "VBUS") (pinfunction "VBUS_VBUS") (pintype "bidirectional"))
    )
    (net (code "46") (name "Net-(R15-Pad2)") (class "Default")
      (node (ref "R15") (pin "2") (pinfunction "2_2") (pintype "passive"))
      (node (ref "R19") (pin "2") (pinfunction "2_2") (pintype "passive"))
      (node (ref "X1") (pin "3") (pinfunction "3_3") (pintype "passive"))
    )
    (net (code "47") (name "Net-(R18-A)") (class "Default")
      (node (ref "R11") (pin "2") (pinfunction "2_2") (pintype "passive"))
      (node (ref "R12") (pin "2") (pinfunction "2_2") (pintype "passive"))
      (node (ref "R18") (pin "1") (pinfunction "A_1") (pintype "passive"))
    )
    (net (code "48") (name "Net-(R21-Pad2)") (class "Default")
      (node (ref "R21") (pin "2") (pinfunction "2_2") (pintype "passive"))
      (node (ref "X2") (pin "D+") (pinfunction "D+_D+") (pintype "bidirectional"))
    )
    (net (code "49") (name "Net-(R22-Pad2)") (class "Default")
      (node (ref "R22") (pin "2") (pinfunction "2_2") (pintype "passive"))
      (node (ref "X2") (pin "D-") (pinfunction "D-_D-") (pintype "bidirectional"))
    )
    (net (code "50") (name "Net-(R23-Pad2)") (class "Default")
      (node (ref "R23") (pin "2") (pinfunction "2_2") (pintype "passive"))
      (node (ref "X2") (pin "ID") (pinfunction "ID_ID") (pintype "bidirectional"))
    )
    (net (code "51") (name "Net-(SW1A-P)") (class "Default")
      (node (ref "SW1") (pin "2") (pinfunction "P_2") (pintype "passive"))
      (node (ref "U1") (pin "3") (pinfunction "EN_3") (pintype "bidirectional"))
    )
    (net (code "52") (name "Net-(U1-SW)") (class "Default")
      (node (ref "L1") (pin "1") (pinfunction "1_1") (pintype "passive"))
      (node (ref "U1") (pin "5") (pinfunction "SW_5") (pintype "bidirectional"))
    )
    (net (code "53") (name "Net-(U2-PROG1)") (class "Default")
      (node (ref "R6") (pin "2") (pinfunction "2_2") (pintype "passive"))
      (node (ref "U2") (pin "13") (pinfunction "PROG1_13") (pintype "bidirectional"))
    )
    (net (code "54") (name "Net-(U2-PROG3)") (class "Default")
      (node (ref "R7") (pin "2") (pinfunction "2_2") (pintype "passive"))
      (node (ref "U2") (pin "12") (pinfunction "PROG3_12") (pintype "bidirectional"))
    )
    (net (code "55") (name "Net-(U2-THERM)") (class "Default")
      (node (ref "R5") (pin "2") (pinfunction "2_2") (pintype "passive"))
      (node (ref "U2") (pin "5") (pinfunction "THERM_5") (pintype "bidirectional"))
    )
    (net (code "56") (name "Net-(U3-OSC_IN(PH0))") (class "Default")
      (node (ref "C10") (pin "1") (pinfunction "1_1") (pintype "passive"))
      (node (ref "U3") (pin "5") (pinfunction "OSC_IN(PH0)_5") (pintype "bidirectional"))
      (node (ref "Y1") (pin "P$1") (pinfunction "1_P$1") (pintype "passive"))
    )
    (net (code "57") (name "Net-(U3-OSC_OUT(PH1))") (class "Default")
      (node (ref "C11") (pin "1") (pinfunction "1_1") (pintype "passive"))
      (node (ref "U3") (pin "6") (pinfunction "OSC_OUT(PH1)_6") (pintype "bidirectional"))
      (node (ref "Y1") (pin "P$2") (pinfunction "2_P$2") (pintype "passive"))
    )
    (net (code "58") (name "Net-(U3-VCAP_1)") (class "Default")
      (node (ref "C12") (pin "1") (pinfunction "1_1") (pintype "passive"))
      (node (ref "U3") (pin "31") (pinfunction "VCAP_1_31") (pintype "bidirectional"))
    )
    (net (code "59") (name "Net-(U3-VCAP_2)") (class "Default")
      (node (ref "C13") (pin "1") (pinfunction "1_1") (pintype "passive"))
      (node (ref "U3") (pin "47") (pinfunction "VCAP_2_47") (pintype "bidirectional"))
    )
    (net (code "60") (name "Net-(U4-OUTVC12)") (class "Default")
      (node (ref "C16") (pin "+") (pinfunction "+_+") (pintype "passive"))
      (node (ref "C17") (pin "1") (pinfunction "1_1") (pintype "passive"))
      (node (ref "U4") (pin "34") (pinfunction "OUTVC12_34") (pintype "power_in"))
    )
    (net (code "61") (name "Net-(U4-VCM)") (class "Default")
      (node (ref "C14") (pin "1") (pinfunction "1_1") (pintype "passive"))
      (node (ref "C15") (pin "+") (pinfunction "+_+") (pintype "passive"))
      (node (ref "U4") (pin "5") (pinfunction "VCM_5") (pintype "output"))
    )
    (net (code "62") (name "Net-(U5-IN+)") (class "Default")
      (node (ref "R16") (pin "1") (pinfunction "1_1") (pintype "passive"))
      (node (ref "U5") (pin "3") (pinfunction "IN+_3") (pintype "input"))
    )
    (net (code "63") (name "Net-(U5-IN-)") (class "Default")
      (node (ref "R17") (pin "1") (pinfunction "1_1") (pintype "passive"))
      (node (ref "U5") (pin "4") (pinfunction "IN-_4") (pintype "input"))
    )
    (net (code "64") (name "VCC") (class "Default")
      (node (ref "C1") (pin "+") (pinfunction "+_+") (pintype "passive"))
      (node (ref "SW1") (pin "1") (pinfunction "S_1") (pintype "passive"))
      (node (ref "U1") (pin "1") (pinfunction "VIN_1") (pintype "bidirectional"))
      (node (ref "U2") (pin "1") (pinfunction "OUT_2_1") (pintype "output"))
      (node (ref "U2") (pin "20") (pinfunction "OUT_20") (pintype "output"))
    )
    (net (code "65") (name "VIN") (class "Default")
      (node (ref "C3") (pin "+") (pinfunction "+_+") (pintype "passive"))
      (node (ref "JP4") (pin "2") (pinfunction "2_2") (pintype "passive"))
      (node (ref "L3") (pin "2") (pinfunction "2_2") (pintype "passive"))
      (node (ref "R3") (pin "1") (pinfunction "1_1") (pintype "passive"))
      (node (ref "U2") (pin "17") (pinfunction "CE_17") (pintype "input"))
      (node (ref "U2") (pin "18") (pinfunction "IN_2_18") (pintype "input"))
      (node (ref "U2") (pin "19") (pinfunction "IN_19") (pintype "input"))
      (node (ref "U2") (pin "4") (pinfunction "PROG2_4") (pintype "input"))
      (node (ref "U3") (pin "42") (pinfunction "VBUS(PA9)_42") (pintype "bidirectional"))
    )
    (net (code "66") (name "unconnected-(U3-PA1-Pad15)") (class "Default")
      (node (ref "U3") (pin "15") (pinfunction "PA1_15") (pintype "bidirectional"))
    )
    (net (code "67") (name "unconnected-(U3-PA4-Pad20)") (class "Default")
      (node (ref "U3") (pin "20") (pinfunction "PA4_20") (pintype "bidirectional"))
    )
    (net (code "68") (name "unconnected-(U3-PA15-Pad50)") (class "Default")
      (node (ref "U3") (pin "50") (pinfunction "PA15_50") (pintype "bidirectional"))
    )
    (net (code "69") (name "unconnected-(U3-PB6-Pad58)") (class "Default")
      (node (ref "U3") (pin "58") (pinfunction "PB6_58") (pintype "bidirectional"))
    )
    (net (code "70") (name "unconnected-(U3-PB7-Pad59)") (class "Default")
      (node (ref "U3") (pin "59") (pinfunction "PB7_59") (pintype "bidirectional"))
    )
    (net (code "71") (name "unconnected-(U3-PB8-Pad61)") (class "Default")
      (node (ref "U3") (pin "61") (pinfunction "PB8_61") (pintype "bidirectional"))
    )
    (net (code "72") (name "unconnected-(U3-PB9-Pad62)") (class "Default")
      (node (ref "U3") (pin "62") (pinfunction "PB9_62") (pintype "bidirectional"))
    )
    (net (code "73") (name "unconnected-(U3-PB11-Pad30)") (class "Default")
      (node (ref "U3") (pin "30") (pinfunction "PB11_30") (pintype "bidirectional"))
    )
    (net (code "74") (name "unconnected-(U3-PB14-Pad35)") (class "Default")
      (node (ref "U3") (pin "35") (pinfunction "PB14_35") (pintype "bidirectional"))
    )
    (net (code "75") (name "unconnected-(U3-PB15-Pad36)") (class "Default")
      (node (ref "U3") (pin "36") (pinfunction "PB15_36") (pintype "bidirectional"))
    )
    (net (code "76") (name "unconnected-(U3-PC6-Pad37)") (class "Default")
      (node (ref "U3") (pin "37") (pinfunction "PC6_37") (pintype "bidirectional"))
    )
    (net (code "77") (name "unconnected-(U3-PC7-Pad38)") (class "Default")
      (node (ref "U3") (pin "38") (pinfunction "PC7_38") (pintype "bidirectional"))
    )
    (net (code "78") (name "unconnected-(U3-PC8-Pad39)") (class "Default")
      (node (ref "U3") (pin "39") (pinfunction "PC8_39") (pintype "bidirectional"))
    )
    (net (code "79") (name "unconnected-(U3-PC9-Pad40)") (class "Default")
      (node (ref "U3") (pin "40") (pinfunction "PC9_40") (pintype "bidirectional"))
    )
    (net (code "80") (name "unconnected-(U3-PC12-Pad53)") (class "Default")
      (node (ref "U3") (pin "53") (pinfunction "PC12_53") (pintype "bidirectional"))
    )
    (net (code "81") (name "unconnected-(U3-PC13-Pad2)") (class "Default")
      (node (ref "U3") (pin "2") (pinfunction "PC13_2") (pintype "bidirectional"))
    )
    (net (code "82") (name "unconnected-(U3-PC14-Pad3)") (class "Default")
      (node (ref "U3") (pin "3") (pinfunction "PC14_3") (pintype "bidirectional"))
    )
    (net (code "83") (name "unconnected-(U3-PD2-Pad54)") (class "Default")
      (node (ref "U3") (pin "54") (pinfunction "PD2_54") (pintype "bidirectional"))
    )
    (net (code "84") (name "unconnected-(U4-D0-Pad24)") (class "Default")
      (node (ref "U4") (pin "24") (pinfunction "D0_24") (pintype "bidirectional"))
    )
    (net (code "85") (name "unconnected-(U4-D1-Pad26)") (class "Default")
      (node (ref "U4") (pin "26") (pinfunction "D1_26") (pintype "bidirectional"))
    )
    (net (code "86") (name "unconnected-(U4-D2-Pad27)") (class "Default")
      (node (ref "U4") (pin "27") (pinfunction "D2_27") (pintype "bidirectional"))
    )
    (net (code "87") (name "unconnected-(U4-D3-Pad28)") (class "Default")
      (node (ref "U4") (pin "28") (pinfunction "D3_28") (pintype "bidirectional"))
    )
    (net (code "88") (name "unconnected-(U4-D4-Pad29)") (class "Default")
      (node (ref "U4") (pin "29") (pinfunction "D4_29") (pintype "bidirectional"))
    )
    (net (code "89") (name "unconnected-(U4-D5-Pad30)") (class "Default")
      (node (ref "U4") (pin "30") (pinfunction "D5_30") (pintype "bidirectional"))
    )
    (net (code "90") (name "unconnected-(U4-D6-Pad32)") (class "Default")
      (node (ref "U4") (pin "32") (pinfunction "D6_32") (pintype "bidirectional"))
    )
    (net (code "91") (name "unconnected-(U4-D7-Pad33)") (class "Default")
      (node (ref "U4") (pin "33") (pinfunction "D7_33") (pintype "bidirectional"))
    )
    (net (code "92") (name "unconnected-(U4-MICIN-Pad7)") (class "Default")
      (node (ref "U4") (pin "7") (pinfunction "MICIN_7") (pintype "input"))
    )
    (net (code "93") (name "unconnected-(U4-TEST-Pad37)") (class "Default")
      (node (ref "U4") (pin "37") (pinfunction "TEST_37") (pintype "input"))
    )
    (net (code "94") (name "unconnected-(U4-VCMHPOUT-Pad3)") (class "Default")
      (node (ref "U4") (pin "3") (pinfunction "VCMHPOUT_3") (pintype "output"))
    )
    (net (code "95") (name "unconnected-(U4-X2-Pad40)") (class "Default")
      (node (ref "U4") (pin "40") (pinfunction "X2_40") (pintype "bidirectional"))
    )
    (net (code "96") (name "unconnected-(U5-NC-Pad2)") (class "Default")
      (node (ref "U5") (pin "2") (pinfunction "NC_2") (pintype "no_connect"))
    )
    (net (code "97") (name "unconnected-(U6-CARD_DETECT1-PadCD2)") (class "Default")
      (node (ref "U6") (pin "CD2") (pinfunction "CARD_DETECT1_CD2") (pintype "passive"))
    )
    (net (code "98") (name "unconnected-(U6-DAT1-Pad8)") (class "Default")
      (node (ref "U6") (pin "8") (pinfunction "DAT1_8") (pintype "bidirectional"))
    )
    (net (code "99") (name "unconnected-(U6-DAT2-Pad1)") (class "Default")
      (node (ref "U6") (pin "1") (pinfunction "DAT2_1") (pintype "bidirectional"))
    )
    (net (code "100") (name "unconnected-(X1-Pad4)") (class "Default")
      (node (ref "X1") (pin "4") (pinfunction "4_4") (pintype "passive"))
    )
  )
)
